# Drive2Pin.net
KiCad netlist of a schematic drawn in Altium Designer
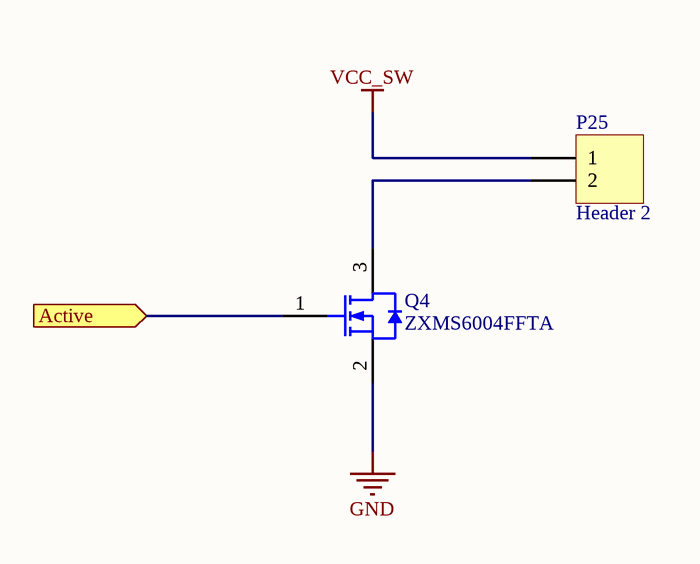
[diagram p0: Drive2Pin.SchDoc]

(export (version "E")
  (design (tool "Eeschema 10.0.6"))
  (components
    (comp (ref "P25")
      (value "Header 2")
      (footprint "HDR1X2")
      (description "Header, 2-Pin")
      (fields (field (name "PUBLISHER") "Altium Limited"))
      (libsource (lib "Miscellaneous Connectors") (part "Header 2"))
    )
    (comp (ref "Q4")
      (value "ZXMS6004FFTA")
      (footprint "DIOD-SOT23F-3_V")
      (fields (field (name "MANUFACTURER") "Diodes Inc"))
      (libsource (lib "Altium Content Vault") (part "NEMOS-GSD-3"))
    )
  )
  (nets
    (net (code "1") (name "/Active") (class "Default")
      (node (ref "Q4") (pin "1") (pinfunction "G_1") (pintype "passive"))
    )
    (net (code "2") (name "GND") (class "Default")
      (node (ref "Q4") (pin "2") (pinfunction "S_2") (pintype "passive"))
    )
    (net (code "3") (name "Net-(Q4-D)") (class "Default")
      (node (ref "P25") (pin "2") (pinfunction "2_2") (pintype "passive"))
      (node (ref "Q4") (pin "3") (pinfunction "D_3") (pintype "passive"))
    )
    (net (code "4") (name "VCC_SW") (class "Default")
      (node (ref "P25") (pin "1") (pinfunction "1_1") (pintype "passive"))
    )
  )
)
